# SCH_hacker-pcb_2023-11-21.net
KiCad netlist of a schematic drawn in EasyEDA
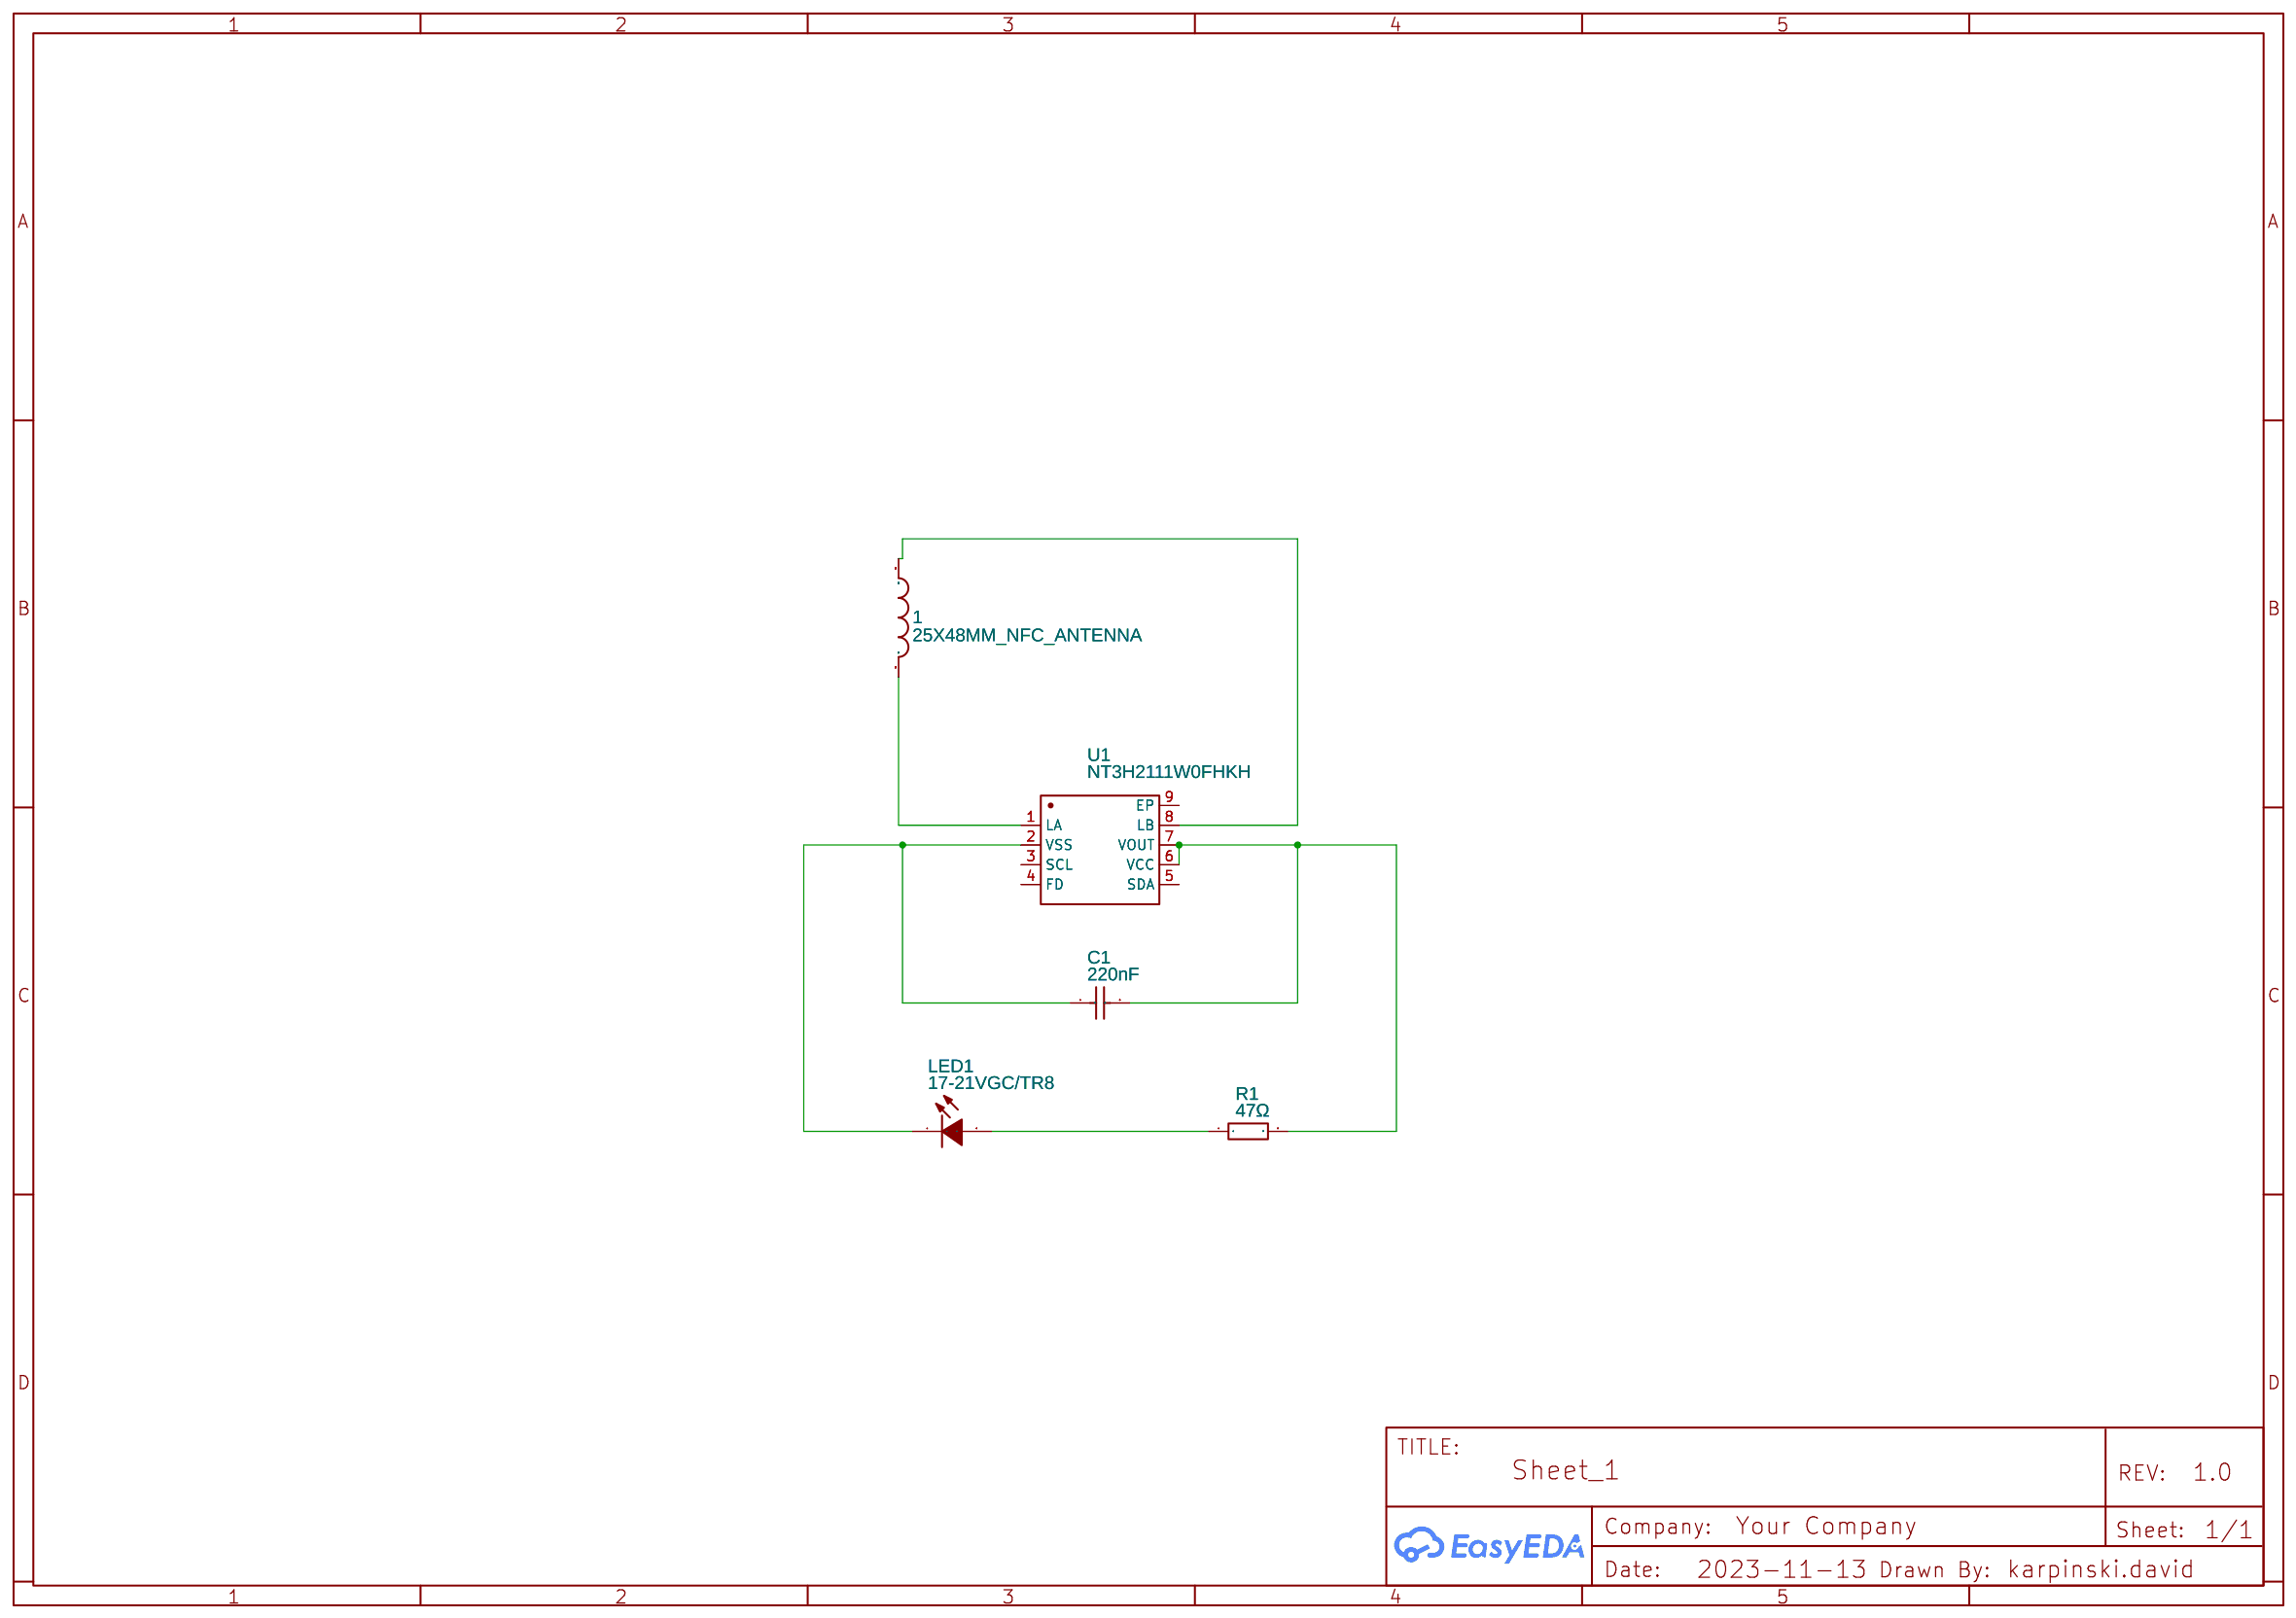
[diagram p0: schematic sheet]

(export (version "E")
  (design (tool "Eeschema 10.0.6"))
  (components
    (comp (ref "1") (value "25X48MM_NFC_ANTENNA") (libsource (lib "") (part "25X48MM_NFC_ANTENNA")))
    (comp (ref "C1")
      (value "220nF")
      (fields
        (field (name "Manufacturer Part") "CL10B224KA8NNNC")
        (field (name "Manufacturer") "SAMSUNG(三星)")
      )
      (libsource (lib "") (part "CL10B224KA8NNNC"))
    )
    (comp (ref "LED1")
      (value "17-21VGC/TR8")
      (fields (field (name "Manufacturer") "EVERLIGHT(亿光)"))
      (libsource (lib "") (part "17-21VGC/TR8"))
    )
    (comp (ref "R1")
      (value "47Ω")
      (fields
        (field (name "Manufacturer Part") "0603WAF470JT5E")
        (field (name "Manufacturer") "UNI-ROYAL(厚声)")
      )
      (libsource (lib "") (part "0603WAF470JT5E"))
    )
    (comp (ref "U1")
      (value "NT3H2111W0FHKH")
      (fields (field (name "Manufacturer") "NXP(恩智浦)"))
      (libsource (lib "") (part "NT3H2111W0FHKH"))
    )
  )
  (nets
    (net (code "1") (name "Net-(LED1-+)") (class "Default")
      (node (ref "LED1") (pin "2") (pinfunction "+_2") (pintype "unspecified"))
      (node (ref "R1") (pin "1") (pinfunction "1_1") (pintype "input"))
    )
    (net (code "2") (name "Net-(LED1--)") (class "Default")
      (node (ref "C1") (pin "1") (pinfunction "1_1") (pintype "input"))
      (node (ref "LED1") (pin "1") (pinfunction "-_1") (pintype "unspecified"))
      (node (ref "U1") (pin "2") (pinfunction "VSS_2") (pintype "unspecified"))
    )
    (net (code "3") (name "Net-(U1-LA)") (class "Default")
      (node (ref "1") (pin "P$2") (pinfunction "P$2_P$2") (pintype "bidirectional"))
      (node (ref "U1") (pin "1") (pinfunction "LA_1") (pintype "unspecified"))
    )
    (net (code "4") (name "Net-(U1-LB)") (class "Default")
      (node (ref "1") (pin "P$1") (pinfunction "P$1_P$1") (pintype "bidirectional"))
      (node (ref "U1") (pin "8") (pinfunction "LB_8") (pintype "unspecified"))
    )
    (net (code "5") (name "Net-(U1-VCC)") (class "Default")
      (node (ref "C1") (pin "2") (pinfunction "2_2") (pintype "input"))
      (node (ref "R1") (pin "2") (pinfunction "2_2") (pintype "input"))
      (node (ref "U1") (pin "6") (pinfunction "VCC_6") (pintype "unspecified"))
      (node (ref "U1") (pin "7") (pinfunction "VOUT_7") (pintype "unspecified"))
    )
    (net (code "6") (name "unconnected-(U1-EP-Pad9)") (class "Default")
      (node (ref "U1") (pin "9") (pinfunction "EP_9") (pintype "unspecified"))
    )
    (net (code "7") (name "unconnected-(U1-FD-Pad4)") (class "Default")
      (node (ref "U1") (pin "4") (pinfunction "FD_4") (pintype "unspecified"))
    )
    (net (code "8") (name "unconnected-(U1-SCL-Pad3)") (class "Default")
      (node (ref "U1") (pin "3") (pinfunction "SCL_3") (pintype "unspecified"))
    )
    (net (code "9") (name "unconnected-(U1-SDA-Pad5)") (class "Default")
      (node (ref "U1") (pin "5") (pinfunction "SDA_5") (pintype "unspecified"))
    )
  )
)
